# Arcade_Kitchen_Timer_Mini.net
KiCad netlist of a schematic drawn in EAGLE
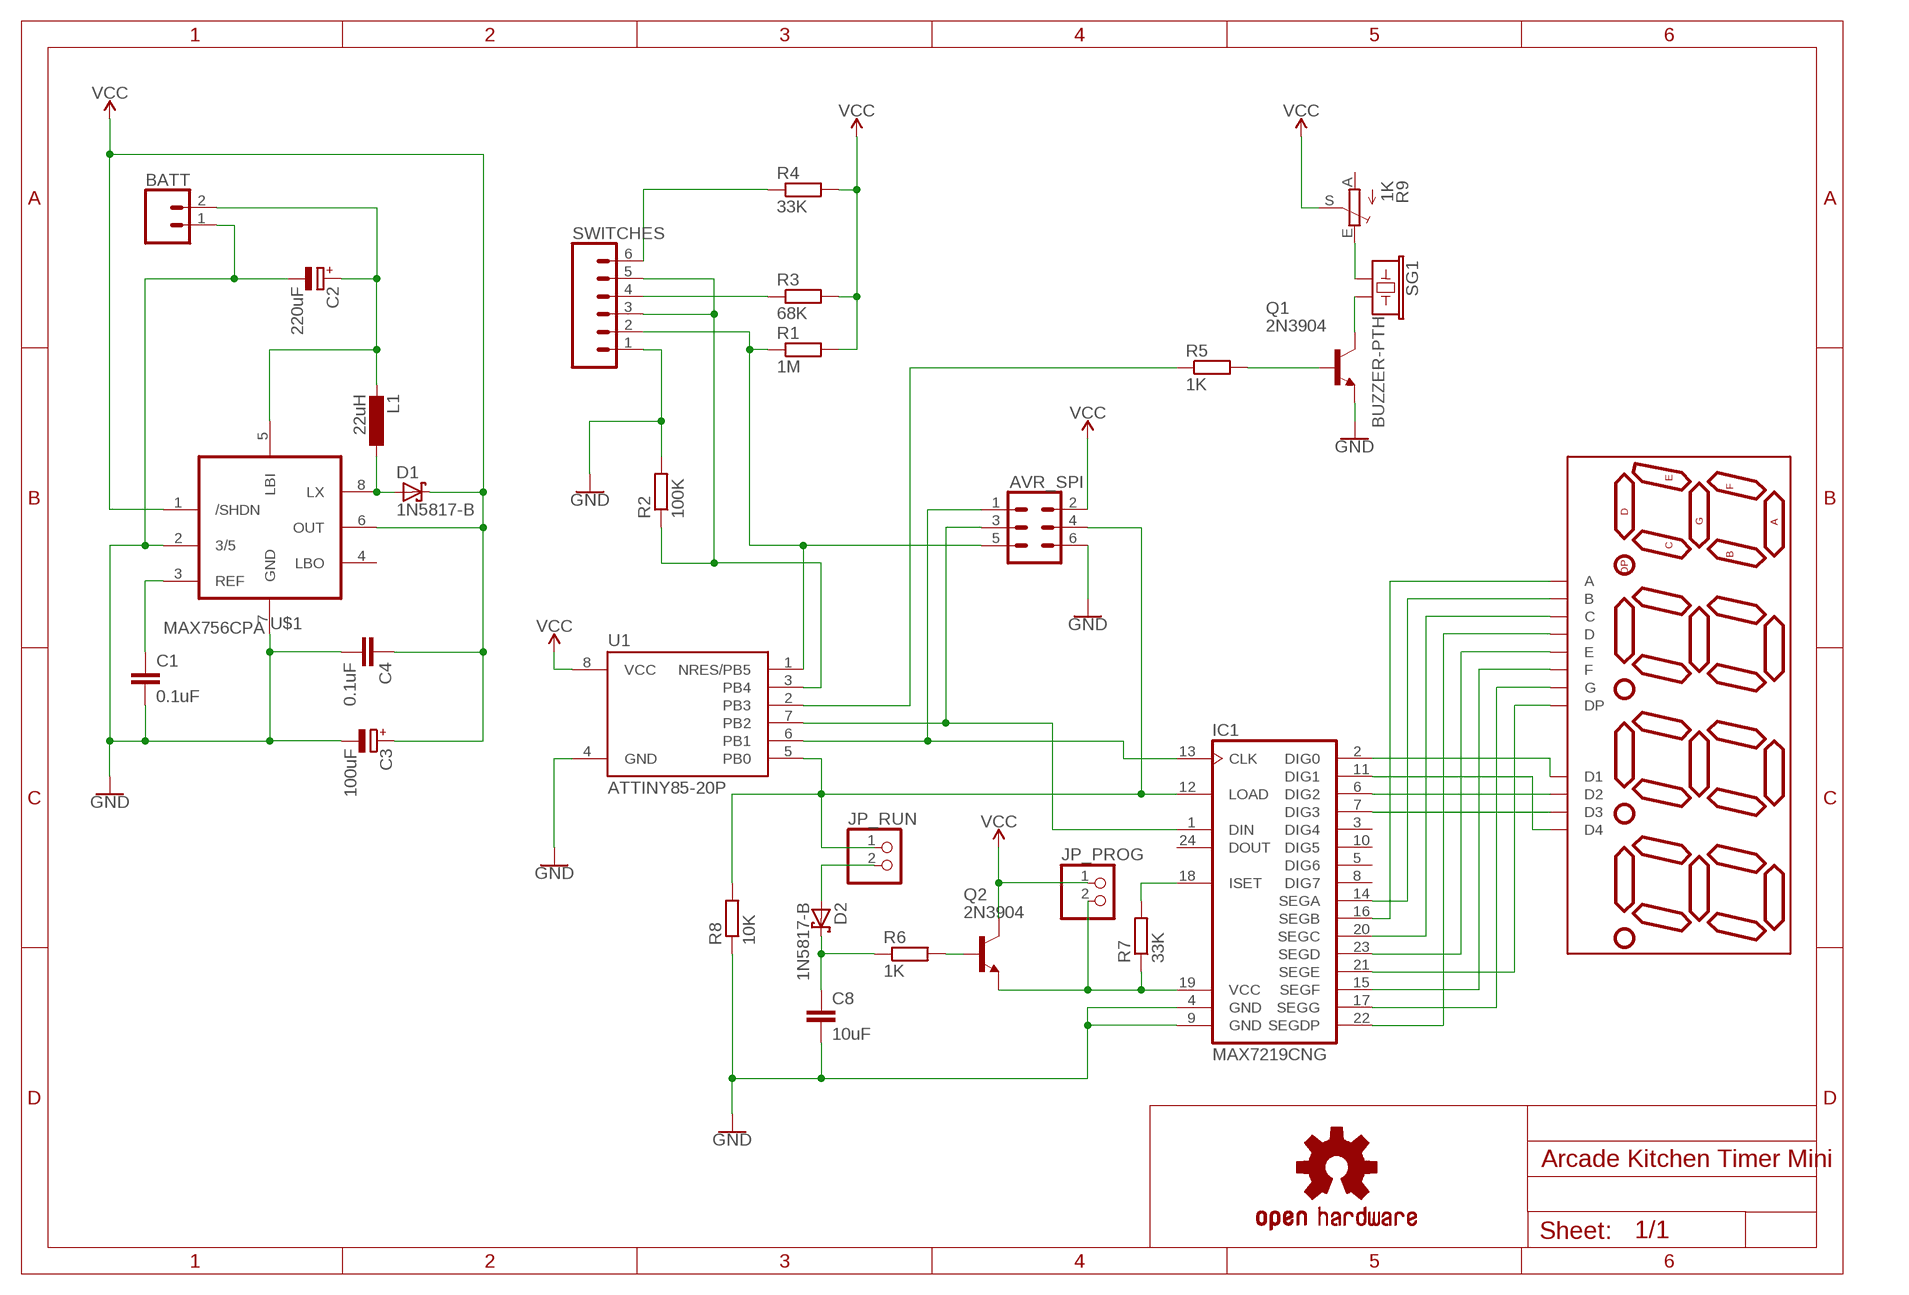
[diagram p0: schematic, sheet 1]

(export (version "E")
  (design (tool "Eeschema 10.0.6"))
  (components
    (comp (ref "AVR_SPI")
      (value "CONN_03X2SHROUD")
      (footprint "eagle-import:2X3-SHROUDED")
      (libsource (lib "eagle-import") (part "CONN_03X2SHROUD"))
    )
    (comp (ref "BATT")
      (value "CONN_02POLAR")
      (footprint "eagle-import:MOLEX-1X2")
      (libsource (lib "eagle-import") (part "CONN_02POLAR"))
    )
    (comp (ref "C1")
      (value "0.1uF")
      (footprint "eagle-import:C050-035X075")
      (libsource (lib "eagle-import") (part "C-EU050-035X075"))
    )
    (comp (ref "C2")
      (value "220uF")
      (footprint "eagle-import:E2,5-7")
      (libsource (lib "eagle-import") (part "CPOL-EUE2.5-7"))
    )
    (comp (ref "C3")
      (value "100uF")
      (footprint "eagle-import:E2,5-6")
      (libsource (lib "eagle-import") (part "CPOL-EUE2.5-6"))
    )
    (comp (ref "C4")
      (value "0.1uF")
      (footprint "eagle-import:C050-035X075")
      (libsource (lib "eagle-import") (part "C-EU050-035X075"))
    )
    (comp (ref "C8")
      (value "10uF")
      (footprint "eagle-import:C050-035X075")
      (libsource (lib "eagle-import") (part "C-EU050-035X075"))
    )
    (comp (ref "D1")
      (value "1N5817-B")
      (footprint "eagle-import:DO41-7.6")
      (libsource (lib "eagle-import") (part "1N5817-B"))
    )
    (comp (ref "D2")
      (value "1N5817-B")
      (footprint "eagle-import:DO41-7.6")
      (libsource (lib "eagle-import") (part "1N5817-B"))
    )
    (comp (ref "DISP1")
      (value "ATA8041ARBJ")
      (footprint "eagle-import:7-SEGMENT-4DIGIT-20MM")
      (libsource (lib "eagle-import") (part "7-SEGMENT-4DIGIT-20MM-RED"))
    )
    (comp (ref "IC1")
      (value "MAX7219CNG")
      (footprint "eagle-import:DIL24-3")
      (fields (field (name "MF") "MAXIM"))
      (libsource (lib "eagle-import") (part "MAX7219CNG"))
    )
    (comp (ref "JP_PROG")
      (value "PINHD-1X2")
      (footprint "eagle-import:1X02")
      (libsource (lib "eagle-import") (part "PINHD-1X2"))
    )
    (comp (ref "JP_RUN")
      (value "PINHD-1X2")
      (footprint "eagle-import:1X02")
      (libsource (lib "eagle-import") (part "PINHD-1X2"))
    )
    (comp (ref "L1")
      (value "22uH")
      (footprint "eagle-import:6000-XXXX-RC")
      (libsource (lib "eagle-import") (part "L-EU6000-XXX-RC"))
    )
    (comp (ref "LOGO1")
      (value "OSHW-LOGOM")
      (footprint "eagle-import:OSHW-LOGO-M")
      (libsource (lib "eagle-import") (part "OSHW-LOGOM"))
    )
    (comp (ref "Q1")
      (value "2N3904")
      (footprint "eagle-import:TO92")
      (libsource (lib "eagle-import") (part "2N3904"))
    )
    (comp (ref "Q2")
      (value "2N3904")
      (footprint "eagle-import:TO92")
      (libsource (lib "eagle-import") (part "2N3904"))
    )
    (comp (ref "R1")
      (value "1M")
      (footprint "eagle-import:0207_10")
      (libsource (lib "eagle-import") (part "R-EU_0207/10"))
    )
    (comp (ref "R2")
      (value "100K")
      (footprint "eagle-import:0207_10")
      (libsource (lib "eagle-import") (part "R-EU_0207/10"))
    )
    (comp (ref "R3")
      (value "68K")
      (footprint "eagle-import:0207_10")
      (libsource (lib "eagle-import") (part "R-EU_0207/10"))
    )
    (comp (ref "R4")
      (value "33K")
      (footprint "eagle-import:0207_10")
      (libsource (lib "eagle-import") (part "R-EU_0207/10"))
    )
    (comp (ref "R5")
      (value "1K")
      (footprint "eagle-import:0207_10")
      (libsource (lib "eagle-import") (part "R-EU_0207/10"))
    )
    (comp (ref "R6")
      (value "1K")
      (footprint "eagle-import:0207_10")
      (libsource (lib "eagle-import") (part "R-EU_0207/10"))
    )
    (comp (ref "R7")
      (value "33K")
      (footprint "eagle-import:0207_10")
      (libsource (lib "eagle-import") (part "R-EU_0207/10"))
    )
    (comp (ref "R8")
      (value "10K")
      (footprint "eagle-import:0207_10")
      (libsource (lib "eagle-import") (part "R-EU_0207/10"))
    )
    (comp (ref "R9")
      (value "1K")
      (footprint "eagle-import:B25P")
      (libsource (lib "eagle-import") (part "TRIM_EU-B25P"))
    )
    (comp (ref "SG1")
      (value "BUZZER-PTH")
      (footprint "eagle-import:BUZZER-12MM")
      (libsource (lib "eagle-import") (part "BUZZER-PTH"))
    )
    (comp (ref "SWITCHES")
      (value "CONN_06POLAR")
      (footprint "eagle-import:MOLEX-1X6")
      (libsource (lib "eagle-import") (part "CONN_06POLAR"))
    )
    (comp (ref "U$1")
      (value "MAX756CPA")
      (footprint "eagle-import:DIL08")
      (libsource (lib "eagle-import") (part "MAX756CPA"))
    )
    (comp (ref "U1")
      (value "ATTINY85-20P")
      (footprint "eagle-import:PDIP08_300MIL")
      (libsource (lib "eagle-import") (part "ATTINY85P-20"))
    )
  )
  (nets
    (net (code "1") (name "GND") (class "Default")
      (node (ref "AVR_SPI") (pin "6") (pinfunction "6_6") (pintype "bidirectional"))
      (node (ref "BATT") (pin "1") (pinfunction "1_1") (pintype "passive"))
      (node (ref "C1") (pin "2") (pinfunction "2_2") (pintype "passive"))
      (node (ref "C2") (pin "-") (pinfunction "-_-") (pintype "passive"))
      (node (ref "C3") (pin "-") (pinfunction "-_-") (pintype "passive"))
      (node (ref "C4") (pin "2") (pinfunction "2_2") (pintype "passive"))
      (node (ref "C8") (pin "2") (pinfunction "2_2") (pintype "passive"))
      (node (ref "IC1") (pin "4") (pinfunction "GND_4") (pintype "power_in"))
      (node (ref "IC1") (pin "9") (pinfunction "GND_9") (pintype "power_in"))
      (node (ref "Q1") (pin "3") (pinfunction "E_3") (pintype "passive"))
      (node (ref "R2") (pin "2") (pinfunction "2_2") (pintype "passive"))
      (node (ref "R8") (pin "1") (pinfunction "1_1") (pintype "passive"))
      (node (ref "SWITCHES") (pin "1") (pinfunction "1_1") (pintype "passive"))
      (node (ref "U$1") (pin "2") (pinfunction "3/5_2") (pintype "bidirectional"))
      (node (ref "U$1") (pin "7") (pinfunction "GND_7") (pintype "power_in"))
      (node (ref "U1") (pin "4") (pinfunction "GND_4") (pintype "power_in"))
    )
    (net (code "2") (name "Net-(C8-Pad1)") (class "Default")
      (node (ref "C8") (pin "1") (pinfunction "1_1") (pintype "passive"))
      (node (ref "D2") (pin "C") (pinfunction "C_C") (pintype "passive"))
      (node (ref "R6") (pin "1") (pinfunction "1_1") (pintype "passive"))
    )
    (net (code "3") (name "Net-(D2-PadA)") (class "Default")
      (node (ref "D2") (pin "A") (pinfunction "A_A") (pintype "passive"))
      (node (ref "JP_RUN") (pin "2") (pinfunction "2_2") (pintype "passive"))
    )
    (net (code "4") (name "Net-(DISP1-A)") (class "Default")
      (node (ref "DISP1") (pin "11") (pinfunction "A_11") (pintype "bidirectional"))
      (node (ref "IC1") (pin "16") (pinfunction "SEGB_16") (pintype "output"))
    )
    (net (code "5") (name "Net-(DISP1-B)") (class "Default")
      (node (ref "DISP1") (pin "7") (pinfunction "B_7") (pintype "bidirectional"))
      (node (ref "IC1") (pin "14") (pinfunction "SEGA_14") (pintype "output"))
    )
    (net (code "6") (name "Net-(DISP1-C)") (class "Default")
      (node (ref "DISP1") (pin "4") (pinfunction "C_4") (pintype "bidirectional"))
      (node (ref "IC1") (pin "20") (pinfunction "SEGC_20") (pintype "output"))
    )
    (net (code "7") (name "Net-(DISP1-D)") (class "Default")
      (node (ref "DISP1") (pin "2") (pinfunction "D_2") (pintype "bidirectional"))
      (node (ref "IC1") (pin "22") (pinfunction "SEGDP_22") (pintype "output"))
    )
    (net (code "8") (name "Net-(DISP1-D1)") (class "Default")
      (node (ref "DISP1") (pin "12") (pinfunction "D1_12") (pintype "bidirectional"))
      (node (ref "IC1") (pin "2") (pinfunction "DIG0_2") (pintype "output"))
    )
    (net (code "9") (name "Net-(DISP1-D2)") (class "Default")
      (node (ref "DISP1") (pin "9") (pinfunction "D2_9") (pintype "bidirectional"))
      (node (ref "IC1") (pin "6") (pinfunction "DIG2_6") (pintype "output"))
    )
    (net (code "10") (name "Net-(DISP1-D3)") (class "Default")
      (node (ref "DISP1") (pin "8") (pinfunction "D3_8") (pintype "bidirectional"))
      (node (ref "IC1") (pin "7") (pinfunction "DIG3_7") (pintype "output"))
    )
    (net (code "11") (name "Net-(DISP1-D4)") (class "Default")
      (node (ref "DISP1") (pin "6") (pinfunction "D4_6") (pintype "bidirectional"))
      (node (ref "IC1") (pin "11") (pinfunction "DIG1_11") (pintype "output"))
    )
    (net (code "12") (name "Net-(DISP1-DP)") (class "Default")
      (node (ref "DISP1") (pin "3") (pinfunction "DP_3") (pintype "bidirectional"))
      (node (ref "IC1") (pin "21") (pinfunction "SEGE_21") (pintype "output"))
    )
    (net (code "13") (name "Net-(DISP1-E)") (class "Default")
      (node (ref "DISP1") (pin "1") (pinfunction "E_1") (pintype "bidirectional"))
      (node (ref "IC1") (pin "23") (pinfunction "SEGD_23") (pintype "output"))
    )
    (net (code "14") (name "Net-(DISP1-F)") (class "Default")
      (node (ref "DISP1") (pin "10") (pinfunction "F_10") (pintype "bidirectional"))
      (node (ref "IC1") (pin "15") (pinfunction "SEGF_15") (pintype "output"))
    )
    (net (code "15") (name "Net-(DISP1-G)") (class "Default")
      (node (ref "DISP1") (pin "5") (pinfunction "G_5") (pintype "bidirectional"))
      (node (ref "IC1") (pin "17") (pinfunction "SEGG_17") (pintype "output"))
    )
    (net (code "16") (name "Net-(IC1-CLK)") (class "Default")
      (node (ref "AVR_SPI") (pin "1") (pinfunction "1_1") (pintype "bidirectional"))
      (node (ref "IC1") (pin "13") (pinfunction "CLK_13") (pintype "input"))
      (node (ref "U1") (pin "6") (pinfunction "PB1_6") (pintype "bidirectional"))
    )
    (net (code "17") (name "Net-(IC1-DIN)") (class "Default")
      (node (ref "AVR_SPI") (pin "3") (pinfunction "3_3") (pintype "bidirectional"))
      (node (ref "IC1") (pin "1") (pinfunction "DIN_1") (pintype "input"))
      (node (ref "U1") (pin "7") (pinfunction "PB2_7") (pintype "bidirectional"))
    )
    (net (code "18") (name "Net-(IC1-ISET)") (class "Default")
      (node (ref "IC1") (pin "18") (pinfunction "ISET_18") (pintype "input"))
      (node (ref "R7") (pin "2") (pinfunction "2_2") (pintype "passive"))
    )
    (net (code "19") (name "Net-(IC1-LOAD)") (class "Default")
      (node (ref "AVR_SPI") (pin "4") (pinfunction "4_4") (pintype "bidirectional"))
      (node (ref "IC1") (pin "12") (pinfunction "LOAD_12") (pintype "input"))
      (node (ref "JP_RUN") (pin "1") (pinfunction "1_1") (pintype "passive"))
      (node (ref "R8") (pin "2") (pinfunction "2_2") (pintype "passive"))
      (node (ref "U1") (pin "5") (pinfunction "PB0_5") (pintype "bidirectional"))
    )
    (net (code "20") (name "Net-(IC1-VCC)") (class "Default")
      (node (ref "IC1") (pin "19") (pinfunction "VCC_19") (pintype "power_in"))
      (node (ref "JP_PROG") (pin "2") (pinfunction "2_2") (pintype "passive"))
      (node (ref "Q2") (pin "3") (pinfunction "E_3") (pintype "passive"))
      (node (ref "R7") (pin "1") (pinfunction "1_1") (pintype "passive"))
    )
    (net (code "21") (name "Net-(Q1-B)") (class "Default")
      (node (ref "Q1") (pin "2") (pinfunction "B_2") (pintype "passive"))
      (node (ref "R5") (pin "2") (pinfunction "2_2") (pintype "passive"))
    )
    (net (code "22") (name "Net-(Q1-C)") (class "Default")
      (node (ref "Q1") (pin "1") (pinfunction "C_1") (pintype "passive"))
      (node (ref "SG1") (pin "-") (pinfunction "2_-") (pintype "passive"))
    )
    (net (code "23") (name "Net-(Q2-B)") (class "Default")
      (node (ref "Q2") (pin "2") (pinfunction "B_2") (pintype "passive"))
      (node (ref "R6") (pin "2") (pinfunction "2_2") (pintype "passive"))
    )
    (net (code "24") (name "Net-(R3-Pad1)") (class "Default")
      (node (ref "R3") (pin "1") (pinfunction "1_1") (pintype "passive"))
      (node (ref "SWITCHES") (pin "4") (pinfunction "4_4") (pintype "passive"))
    )
    (net (code "25") (name "Net-(R4-Pad1)") (class "Default")
      (node (ref "R4") (pin "1") (pinfunction "1_1") (pintype "passive"))
      (node (ref "SWITCHES") (pin "6") (pinfunction "6_6") (pintype "passive"))
    )
    (net (code "26") (name "Net-(SG1-1)") (class "Default")
      (node (ref "R9") (pin "E") (pinfunction "E_E") (pintype "passive"))
      (node (ref "SG1") (pin "+") (pinfunction "1_+") (pintype "passive"))
    )
    (net (code "27") (name "Net-(U$1-LBI)") (class "Default")
      (node (ref "BATT") (pin "2") (pinfunction "2_2") (pintype "passive"))
      (node (ref "C2") (pin "+") (pinfunction "+_+") (pintype "passive"))
      (node (ref "L1") (pin "2") (pinfunction "2_2") (pintype "passive"))
      (node (ref "U$1") (pin "5") (pinfunction "LBI_5") (pintype "input"))
    )
    (net (code "28") (name "Net-(U$1-LX)") (class "Default")
      (node (ref "D1") (pin "A") (pinfunction "A_A") (pintype "passive"))
      (node (ref "L1") (pin "1") (pinfunction "1_1") (pintype "passive"))
      (node (ref "U$1") (pin "8") (pinfunction "LX_8") (pintype "output"))
    )
    (net (code "29") (name "Net-(U$1-REF)") (class "Default")
      (node (ref "C1") (pin "1") (pinfunction "1_1") (pintype "passive"))
      (node (ref "U$1") (pin "3") (pinfunction "REF_3") (pintype "passive"))
    )
    (net (code "30") (name "Net-(U1-NRES{slash}PB5)") (class "Default")
      (node (ref "AVR_SPI") (pin "5") (pinfunction "5_5") (pintype "bidirectional"))
      (node (ref "R1") (pin "1") (pinfunction "1_1") (pintype "passive"))
      (node (ref "SWITCHES") (pin "2") (pinfunction "2_2") (pintype "passive"))
      (node (ref "U1") (pin "1") (pinfunction "NRES/PB5_1") (pintype "bidirectional"))
    )
    (net (code "31") (name "Net-(U1-PB3)") (class "Default")
      (node (ref "R5") (pin "1") (pinfunction "1_1") (pintype "passive"))
      (node (ref "U1") (pin "2") (pinfunction "PB3_2") (pintype "bidirectional"))
    )
    (net (code "32") (name "Net-(U1-PB4)") (class "Default")
      (node (ref "R2") (pin "1") (pinfunction "1_1") (pintype "passive"))
      (node (ref "SWITCHES") (pin "3") (pinfunction "3_3") (pintype "passive"))
      (node (ref "SWITCHES") (pin "5") (pinfunction "5_5") (pintype "passive"))
      (node (ref "U1") (pin "3") (pinfunction "PB4_3") (pintype "bidirectional"))
    )
    (net (code "33") (name "VCC") (class "Default")
      (node (ref "AVR_SPI") (pin "2") (pinfunction "2_2") (pintype "bidirectional"))
      (node (ref "C3") (pin "+") (pinfunction "+_+") (pintype "passive"))
      (node (ref "C4") (pin "1") (pinfunction "1_1") (pintype "passive"))
      (node (ref "D1") (pin "C") (pinfunction "C_C") (pintype "passive"))
      (node (ref "JP_PROG") (pin "1") (pinfunction "1_1") (pintype "passive"))
      (node (ref "Q2") (pin "1") (pinfunction "C_1") (pintype "passive"))
      (node (ref "R1") (pin "2") (pinfunction "2_2") (pintype "passive"))
      (node (ref "R3") (pin "2") (pinfunction "2_2") (pintype "passive"))
      (node (ref "R4") (pin "2") (pinfunction "2_2") (pintype "passive"))
      (node (ref "R9") (pin "S") (pinfunction "S_S") (pintype "passive"))
      (node (ref "U$1") (pin "1") (pinfunction "/SHDN_1") (pintype "input"))
      (node (ref "U$1") (pin "6") (pinfunction "OUT_6") (pintype "output"))
      (node (ref "U1") (pin "8") (pinfunction "VCC_8") (pintype "power_in"))
    )
    (net (code "34") (name "unconnected-(IC1-DIG4-Pad3)") (class "Default")
      (node (ref "IC1") (pin "3") (pinfunction "DIG4_3") (pintype "output"))
    )
    (net (code "35") (name "unconnected-(IC1-DIG5-Pad10)") (class "Default")
      (node (ref "IC1") (pin "10") (pinfunction "DIG5_10") (pintype "output"))
    )
    (net (code "36") (name "unconnected-(IC1-DIG6-Pad5)") (class "Default")
      (node (ref "IC1") (pin "5") (pinfunction "DIG6_5") (pintype "output"))
    )
    (net (code "37") (name "unconnected-(IC1-DIG7-Pad8)") (class "Default")
      (node (ref "IC1") (pin "8") (pinfunction "DIG7_8") (pintype "output"))
    )
    (net (code "38") (name "unconnected-(IC1-DOUT-Pad24)") (class "Default")
      (node (ref "IC1") (pin "24") (pinfunction "DOUT_24") (pintype "output"))
    )
    (net (code "39") (name "unconnected-(R9-PadA)") (class "Default")
      (node (ref "R9") (pin "A") (pinfunction "A_A") (pintype "passive"))
    )
    (net (code "40") (name "unconnected-(U$1-LBO-Pad4)") (class "Default")
      (node (ref "U$1") (pin "4") (pinfunction "LBO_4") (pintype "input"))
    )
  )
)
